# MAX_7SEG_USBC.net
KiCad netlist of a schematic drawn in Altium Designer
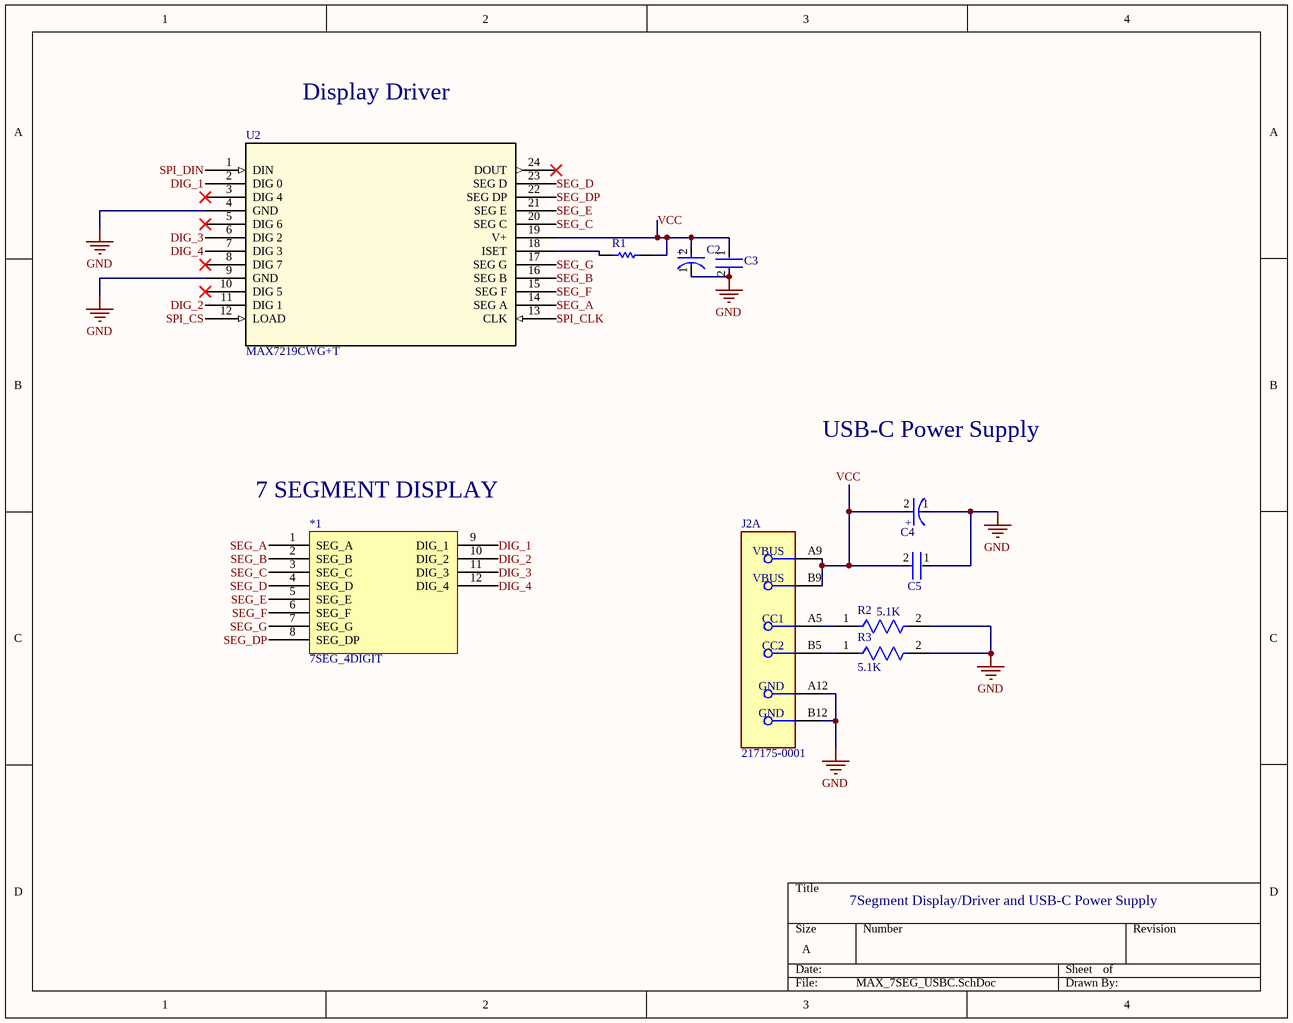
[diagram p0: MAX_7SEG_USBC.SchDoc]

(export (version "E")
  (design (tool "Eeschema 10.0.6"))
  (components
    (comp (ref "*1")
      (value "7SEG_4DIGIT")
      (footprint "PCBComponent_1")
      (description "4 Digit 7 Segment Common Cathode Display")
      (libsource (lib "7SEF_4DIGIT") (part "7SEG_4DIGIT"))
    )
    (comp (ref "C2")
      (value "TAJB106K010RNJ")
      (footprint "FP-TAJB-MFG")
      (description "10uF 10V  ±10% 2.1Ω 1210  SMD Tantalum Capacitor")
      (fields (field (name "TOLERANCE") "10%") (field (name "VOLTAGE") "10V"))
      (libsource (lib "Altium Content Vault") (part "203bc49f2ac43e59fd269a8c329ed05"))
    )
    (comp (ref "C3")
      (value "GRM155R71C104KA88D")
      (footprint "FP-GRM15-MFG")
      (description "CAP CER 0.1UF 16V X7R 0402")
      (fields
        (field (name "TOLERANCE") "10%")
        (field (name "OCTOPART") "https://octopart.com/grm155r71c104ka88d-murata-196880")
      )
      (libsource (lib "Altium Content Vault") (part "236180d848d6139a670b325ea6854c9"))
    )
    (comp (ref "C4")
      (value "TAJB106K010RNJ")
      (footprint "FP-TAJB-MFG")
      (description "10uF 10V  ±10% 2.1Ω 1210  SMD Tantalum Capacitor")
      (fields (field (name "TOLERANCE") "10%") (field (name "VOLTAGE") "10V"))
      (libsource (lib "Altium Content Vault") (part "203bc49f2ac43e59fd269a8c329ed05"))
    )
    (comp (ref "C5")
      (value "GRM155R71C104KA88D")
      (footprint "FP-GRM15-MFG")
      (description "CAP CER 0.1UF 16V X7R 0402")
      (fields
        (field (name "TOLERANCE") "10%")
        (field (name "OCTOPART") "https://octopart.com/grm155r71c104ka88d-murata-196880")
      )
      (libsource (lib "Altium Content Vault") (part "236180d848d6139a670b325ea6854c9"))
    )
    (comp (ref "J2")
      (value "217175-0001")
      (footprint "FP-217175-0001-MFG")
      (description "CONN RCP USB2.0 C 6+18P SMD RA")
      (libsource (lib "Altium Content Vault") (part "6a66c69350f09309f94811689c98437"))
    )
    (comp (ref "R1")
      (value "RC0402FR-0710KL")
      (footprint "RESC1005X40X25LL05T10")
      (fields (field (name "MANUFACTURER") "Yageo / Phycomp"))
      (libsource (lib "Altium Content Vault") (part "RES"))
    )
    (comp (ref "R2")
      (value "5.1K")
      (footprint "FP-RN73R1E-IPC_C")
      (description "5.1kΩ ±1% 0.063W, 1/16W Chip Resistor 0402 (1005 Metric) Moisture Resistant Thin Film")
      (libsource (lib "Altium Content Vault") (part "1029c3af85768c4190bb7ad29bc67b5"))
    )
    (comp (ref "R3")
      (value "5.1K")
      (footprint "FP-RN73R1E-IPC_C")
      (description "5.1kΩ ±1% 0.063W, 1/16W Chip Resistor 0402 (1005 Metric) Moisture Resistant Thin Film")
      (libsource (lib "Altium Content Vault") (part "1029c3af85768c4190bb7ad29bc67b5"))
    )
    (comp (ref "U2")
      (value "MAX7219CWG+T")
      (footprint "21-0042B_24_MXM")
      (description "Serially Interfaced, 8-Digit, LED Display Drivers")
      (fields (field (name "COPYRIGHT") "Copyright (C) 2026 Ultra Librarian. All rights reserved."))
      (libsource (lib "MAX7219CWG&plus_T") (part "MAX7219CWG+T"))
    )
  )
  (nets
    (net (code "1") (name "/DIG_1") (class "Default")
      (node (ref "*1") (pin "9") (pinfunction "DIG_1_9") (pintype "passive"))
      (node (ref "U2") (pin "2") (pinfunction "DIG_0_2") (pintype "passive"))
    )
    (net (code "2") (name "/DIG_2") (class "Default")
      (node (ref "*1") (pin "10") (pinfunction "DIG_2_10") (pintype "passive"))
      (node (ref "U2") (pin "11") (pinfunction "DIG_1_11") (pintype "passive"))
    )
    (net (code "3") (name "/DIG_3") (class "Default")
      (node (ref "*1") (pin "11") (pinfunction "DIG_3_11") (pintype "passive"))
      (node (ref "U2") (pin "6") (pinfunction "DIG_2_6") (pintype "passive"))
    )
    (net (code "4") (name "/DIG_4") (class "Default")
      (node (ref "*1") (pin "12") (pinfunction "DIG_4_12") (pintype "passive"))
      (node (ref "U2") (pin "7") (pinfunction "DIG_3_7") (pintype "passive"))
    )
    (net (code "5") (name "/SEG_A") (class "Default")
      (node (ref "*1") (pin "1") (pinfunction "SEG_A_1") (pintype "passive"))
      (node (ref "U2") (pin "14") (pinfunction "SEG_A_14") (pintype "passive"))
    )
    (net (code "6") (name "/SEG_B") (class "Default")
      (node (ref "*1") (pin "2") (pinfunction "SEG_B_2") (pintype "passive"))
      (node (ref "U2") (pin "16") (pinfunction "SEG_B_16") (pintype "passive"))
    )
    (net (code "7") (name "/SEG_C") (class "Default")
      (node (ref "*1") (pin "3") (pinfunction "SEG_C_3") (pintype "passive"))
      (node (ref "U2") (pin "20") (pinfunction "SEG_C_20") (pintype "passive"))
    )
    (net (code "8") (name "/SEG_D") (class "Default")
      (node (ref "*1") (pin "4") (pinfunction "SEG_D_4") (pintype "passive"))
      (node (ref "U2") (pin "23") (pinfunction "SEG_D_23") (pintype "passive"))
    )
    (net (code "9") (name "/SEG_DP") (class "Default")
      (node (ref "*1") (pin "8") (pinfunction "SEG_DP_8") (pintype "passive"))
      (node (ref "U2") (pin "22") (pinfunction "SEG_DP_22") (pintype "passive"))
    )
    (net (code "10") (name "/SEG_E") (class "Default")
      (node (ref "*1") (pin "5") (pinfunction "SEG_E_5") (pintype "passive"))
      (node (ref "U2") (pin "21") (pinfunction "SEG_E_21") (pintype "passive"))
    )
    (net (code "11") (name "/SEG_F") (class "Default")
      (node (ref "*1") (pin "6") (pinfunction "SEG_F_6") (pintype "passive"))
      (node (ref "U2") (pin "15") (pinfunction "SEG_F_15") (pintype "passive"))
    )
    (net (code "12") (name "/SEG_G") (class "Default")
      (node (ref "*1") (pin "7") (pinfunction "SEG_G_7") (pintype "passive"))
      (node (ref "U2") (pin "17") (pinfunction "SEG_G_17") (pintype "passive"))
    )
    (net (code "13") (name "/SPI_CLK") (class "Default")
      (node (ref "U2") (pin "13") (pinfunction "CLK_13") (pintype "input"))
    )
    (net (code "14") (name "/SPI_CS") (class "Default")
      (node (ref "U2") (pin "12") (pinfunction "LOAD_12") (pintype "input"))
    )
    (net (code "15") (name "/SPI_DIN") (class "Default")
      (node (ref "U2") (pin "1") (pinfunction "DIN_1") (pintype "input"))
    )
    (net (code "16") (name "/VCC") (class "Default")
      (node (ref "C2") (pin "2") (pinfunction "A_2") (pintype "passive"))
      (node (ref "C3") (pin "1") (pinfunction "1_1") (pintype "passive"))
      (node (ref "C4") (pin "2") (pinfunction "A_2") (pintype "passive"))
      (node (ref "C5") (pin "2") (pinfunction "2_2") (pintype "passive"))
      (node (ref "J2") (pin "A9") (pinfunction "VBUS_A9") (pintype "power_in"))
      (node (ref "J2") (pin "B9") (pinfunction "VBUS_B9") (pintype "power_in"))
      (node (ref "R1") (pin "2") (pinfunction "2_2") (pintype "passive"))
      (node (ref "U2") (pin "19") (pinfunction "V+_19") (pintype "power_in"))
    )
    (net (code "17") (name "GND") (class "Default")
      (node (ref "C2") (pin "1") (pinfunction "C_1") (pintype "passive"))
      (node (ref "C3") (pin "2") (pinfunction "2_2") (pintype "passive"))
      (node (ref "C4") (pin "1") (pinfunction "C_1") (pintype "passive"))
      (node (ref "C5") (pin "1") (pinfunction "1_1") (pintype "passive"))
      (node (ref "J2") (pin "A12") (pinfunction "GND_A12") (pintype "power_in"))
      (node (ref "J2") (pin "B12") (pinfunction "GND_B12") (pintype "power_in"))
      (node (ref "R2") (pin "2") (pinfunction "2_2") (pintype "passive"))
      (node (ref "R3") (pin "2") (pinfunction "2_2") (pintype "passive"))
      (node (ref "U2") (pin "4") (pinfunction "GND_4") (pintype "power_in"))
      (node (ref "U2") (pin "9") (pinfunction "GND_9") (pintype "power_in"))
    )
    (net (code "18") (name "Net-(J2A-CC1)") (class "Default")
      (node (ref "J2") (pin "A5") (pinfunction "CC1_A5") (pintype "passive"))
      (node (ref "R2") (pin "1") (pinfunction "1_1") (pintype "passive"))
    )
    (net (code "19") (name "Net-(J2A-CC2)") (class "Default")
      (node (ref "J2") (pin "B5") (pinfunction "CC2_B5") (pintype "passive"))
      (node (ref "R3") (pin "1") (pinfunction "1_1") (pintype "passive"))
    )
    (net (code "20") (name "Net-(U2-ISET)") (class "Default")
      (node (ref "R1") (pin "1") (pinfunction "1_1") (pintype "passive"))
      (node (ref "U2") (pin "18") (pinfunction "ISET_18") (pintype "passive"))
    )
    (net (code "21") (name "unconnected-(U2-DIG_4-Pad3)") (class "Default")
      (node (ref "U2") (pin "3") (pinfunction "DIG_4_3") (pintype "passive+no_connect"))
    )
    (net (code "22") (name "unconnected-(U2-DIG_5-Pad10)") (class "Default")
      (node (ref "U2") (pin "10") (pinfunction "DIG_5_10") (pintype "passive+no_connect"))
    )
    (net (code "23") (name "unconnected-(U2-DIG_6-Pad5)") (class "Default")
      (node (ref "U2") (pin "5") (pinfunction "DIG_6_5") (pintype "passive+no_connect"))
    )
    (net (code "24") (name "unconnected-(U2-DIG_7-Pad8)") (class "Default")
      (node (ref "U2") (pin "8") (pinfunction "DIG_7_8") (pintype "passive+no_connect"))
    )
    (net (code "25") (name "unconnected-(U2-DOUT-Pad24)") (class "Default")
      (node (ref "U2") (pin "24") (pinfunction "DOUT_24") (pintype "output+no_connect"))
    )
  )
)
